# eprom-programmer.net
KiCad netlist of a schematic drawn in EAGLE
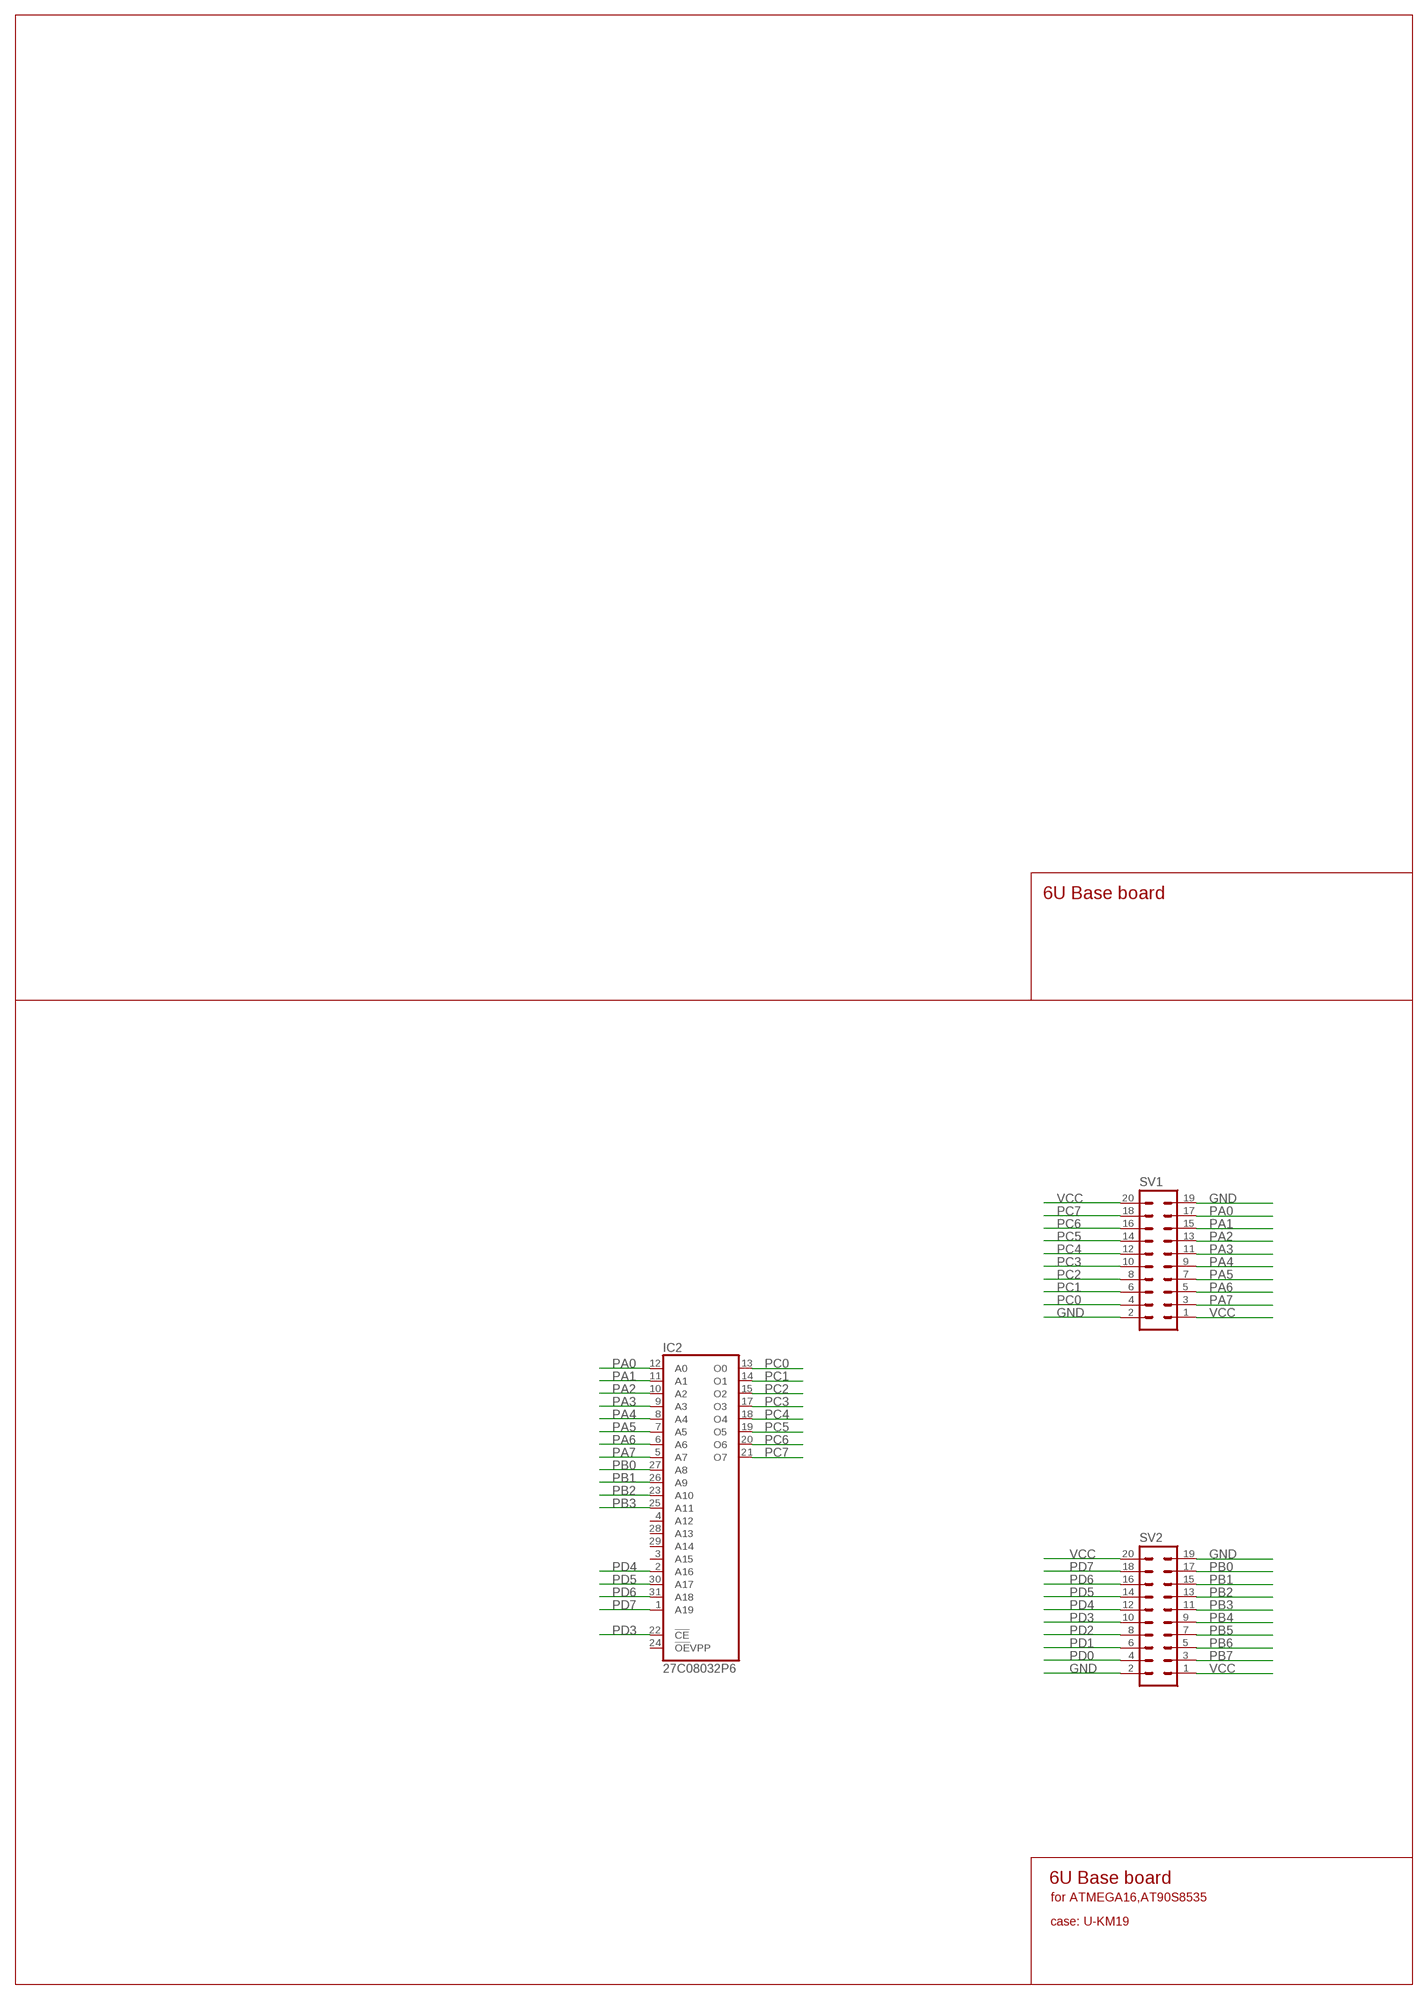
[diagram p0: schematic, sheet 1]

(export (version "E")
  (design (tool "Eeschema 10.0.6"))
  (components
    (comp (ref "IC2")
      (value "27C08032P6")
      (footprint "eagle-import:DIL32")
      (fields (field (name "MPN") "AT27C080-90PU"))
      (libsource (lib "eagle-import") (part "27C08032P6"))
    )
    (comp (ref "SV1")
      (value "MA10-2")
      (footprint "eagle-import:MA10-2")
      (libsource (lib "eagle-import") (part "MA10-2"))
    )
    (comp (ref "SV2")
      (value "MA10-2")
      (footprint "eagle-import:MA10-2")
      (libsource (lib "eagle-import") (part "MA10-2"))
    )
  )
  (nets
    (net (code "1") (name "/GND") (class "Default")
      (node (ref "SV1") (pin "19") (pinfunction "19_19") (pintype "passive"))
      (node (ref "SV1") (pin "2") (pinfunction "2_2") (pintype "passive"))
      (node (ref "SV2") (pin "19") (pinfunction "19_19") (pintype "passive"))
      (node (ref "SV2") (pin "2") (pinfunction "2_2") (pintype "passive"))
    )
    (net (code "2") (name "/PA0") (class "Default")
      (node (ref "IC2") (pin "12") (pinfunction "A0_12") (pintype "input"))
      (node (ref "SV1") (pin "17") (pinfunction "17_17") (pintype "passive"))
    )
    (net (code "3") (name "/PA1") (class "Default")
      (node (ref "IC2") (pin "11") (pinfunction "A1_11") (pintype "input"))
      (node (ref "SV1") (pin "15") (pinfunction "15_15") (pintype "passive"))
    )
    (net (code "4") (name "/PA2") (class "Default")
      (node (ref "IC2") (pin "10") (pinfunction "A2_10") (pintype "input"))
      (node (ref "SV1") (pin "13") (pinfunction "13_13") (pintype "passive"))
    )
    (net (code "5") (name "/PA3") (class "Default")
      (node (ref "IC2") (pin "9") (pinfunction "A3_9") (pintype "input"))
      (node (ref "SV1") (pin "11") (pinfunction "11_11") (pintype "passive"))
    )
    (net (code "6") (name "/PA4") (class "Default")
      (node (ref "IC2") (pin "8") (pinfunction "A4_8") (pintype "input"))
      (node (ref "SV1") (pin "9") (pinfunction "9_9") (pintype "passive"))
    )
    (net (code "7") (name "/PA5") (class "Default")
      (node (ref "IC2") (pin "7") (pinfunction "A5_7") (pintype "input"))
      (node (ref "SV1") (pin "7") (pinfunction "7_7") (pintype "passive"))
    )
    (net (code "8") (name "/PA6") (class "Default")
      (node (ref "IC2") (pin "6") (pinfunction "A6_6") (pintype "input"))
      (node (ref "SV1") (pin "5") (pinfunction "5_5") (pintype "passive"))
    )
    (net (code "9") (name "/PA7") (class "Default")
      (node (ref "IC2") (pin "5") (pinfunction "A7_5") (pintype "input"))
      (node (ref "SV1") (pin "3") (pinfunction "3_3") (pintype "passive"))
    )
    (net (code "10") (name "/PB0") (class "Default")
      (node (ref "IC2") (pin "27") (pinfunction "A8_27") (pintype "input"))
      (node (ref "SV2") (pin "17") (pinfunction "17_17") (pintype "passive"))
    )
    (net (code "11") (name "/PB1") (class "Default")
      (node (ref "IC2") (pin "26") (pinfunction "A9_26") (pintype "input"))
      (node (ref "SV2") (pin "15") (pinfunction "15_15") (pintype "passive"))
    )
    (net (code "12") (name "/PB2") (class "Default")
      (node (ref "IC2") (pin "23") (pinfunction "A10_23") (pintype "input"))
      (node (ref "SV2") (pin "13") (pinfunction "13_13") (pintype "passive"))
    )
    (net (code "13") (name "/PB3") (class "Default")
      (node (ref "IC2") (pin "25") (pinfunction "A11_25") (pintype "input"))
      (node (ref "SV2") (pin "11") (pinfunction "11_11") (pintype "passive"))
    )
    (net (code "14") (name "/PB4") (class "Default")
      (node (ref "SV2") (pin "9") (pinfunction "9_9") (pintype "passive"))
    )
    (net (code "15") (name "/PB5") (class "Default")
      (node (ref "SV2") (pin "7") (pinfunction "7_7") (pintype "passive"))
    )
    (net (code "16") (name "/PB6") (class "Default")
      (node (ref "SV2") (pin "5") (pinfunction "5_5") (pintype "passive"))
    )
    (net (code "17") (name "/PB7") (class "Default")
      (node (ref "SV2") (pin "3") (pinfunction "3_3") (pintype "passive"))
    )
    (net (code "18") (name "/PC0") (class "Default")
      (node (ref "IC2") (pin "13") (pinfunction "O0_13") (pintype "tri_state"))
      (node (ref "SV1") (pin "4") (pinfunction "4_4") (pintype "passive"))
    )
    (net (code "19") (name "/PC1") (class "Default")
      (node (ref "IC2") (pin "14") (pinfunction "O1_14") (pintype "tri_state"))
      (node (ref "SV1") (pin "6") (pinfunction "6_6") (pintype "passive"))
    )
    (net (code "20") (name "/PC2") (class "Default")
      (node (ref "IC2") (pin "15") (pinfunction "O2_15") (pintype "tri_state"))
      (node (ref "SV1") (pin "8") (pinfunction "8_8") (pintype "passive"))
    )
    (net (code "21") (name "/PC3") (class "Default")
      (node (ref "IC2") (pin "17") (pinfunction "O3_17") (pintype "tri_state"))
      (node (ref "SV1") (pin "10") (pinfunction "10_10") (pintype "passive"))
    )
    (net (code "22") (name "/PC4") (class "Default")
      (node (ref "IC2") (pin "18") (pinfunction "O4_18") (pintype "tri_state"))
      (node (ref "SV1") (pin "12") (pinfunction "12_12") (pintype "passive"))
    )
    (net (code "23") (name "/PC5") (class "Default")
      (node (ref "IC2") (pin "19") (pinfunction "O5_19") (pintype "tri_state"))
      (node (ref "SV1") (pin "14") (pinfunction "14_14") (pintype "passive"))
    )
    (net (code "24") (name "/PC6") (class "Default")
      (node (ref "IC2") (pin "20") (pinfunction "O6_20") (pintype "tri_state"))
      (node (ref "SV1") (pin "16") (pinfunction "16_16") (pintype "passive"))
    )
    (net (code "25") (name "/PC7") (class "Default")
      (node (ref "IC2") (pin "21") (pinfunction "O7_21") (pintype "tri_state"))
      (node (ref "SV1") (pin "18") (pinfunction "18_18") (pintype "passive"))
    )
    (net (code "26") (name "/PD0") (class "Default")
      (node (ref "SV2") (pin "4") (pinfunction "4_4") (pintype "passive"))
    )
    (net (code "27") (name "/PD1") (class "Default")
      (node (ref "SV2") (pin "6") (pinfunction "6_6") (pintype "passive"))
    )
    (net (code "28") (name "/PD2") (class "Default")
      (node (ref "SV2") (pin "8") (pinfunction "8_8") (pintype "passive"))
    )
    (net (code "29") (name "/PD3") (class "Default")
      (node (ref "IC2") (pin "22") (pinfunction "~{CE}_22") (pintype "input"))
      (node (ref "SV2") (pin "10") (pinfunction "10_10") (pintype "passive"))
    )
    (net (code "30") (name "/PD4") (class "Default")
      (node (ref "IC2") (pin "2") (pinfunction "A16_2") (pintype "input"))
      (node (ref "SV2") (pin "12") (pinfunction "12_12") (pintype "passive"))
    )
    (net (code "31") (name "/PD5") (class "Default")
      (node (ref "IC2") (pin "30") (pinfunction "A17_30") (pintype "input"))
      (node (ref "SV2") (pin "14") (pinfunction "14_14") (pintype "passive"))
    )
    (net (code "32") (name "/PD6") (class "Default")
      (node (ref "IC2") (pin "31") (pinfunction "A18_31") (pintype "input"))
      (node (ref "SV2") (pin "16") (pinfunction "16_16") (pintype "passive"))
    )
    (net (code "33") (name "/PD7") (class "Default")
      (node (ref "IC2") (pin "1") (pinfunction "A19_1") (pintype "input"))
      (node (ref "SV2") (pin "18") (pinfunction "18_18") (pintype "passive"))
    )
    (net (code "34") (name "/VCC") (class "Default")
      (node (ref "SV1") (pin "1") (pinfunction "1_1") (pintype "passive"))
      (node (ref "SV1") (pin "20") (pinfunction "20_20") (pintype "passive"))
      (node (ref "SV2") (pin "1") (pinfunction "1_1") (pintype "passive"))
      (node (ref "SV2") (pin "20") (pinfunction "20_20") (pintype "passive"))
    )
    (net (code "35") (name "unconnected-(IC2A-A12-Pad4)") (class "Default")
      (node (ref "IC2") (pin "4") (pinfunction "A12_4") (pintype "input"))
    )
    (net (code "36") (name "unconnected-(IC2A-A13-Pad28)") (class "Default")
      (node (ref "IC2") (pin "28") (pinfunction "A13_28") (pintype "input"))
    )
    (net (code "37") (name "unconnected-(IC2A-A14-Pad29)") (class "Default")
      (node (ref "IC2") (pin "29") (pinfunction "A14_29") (pintype "input"))
    )
    (net (code "38") (name "unconnected-(IC2A-A15-Pad3)") (class "Default")
      (node (ref "IC2") (pin "3") (pinfunction "A15_3") (pintype "input"))
    )
    (net (code "39") (name "unconnected-(IC2A-~{OE}VPP-Pad24)") (class "Default")
      (node (ref "IC2") (pin "24") (pinfunction "~{OE}VPP_24") (pintype "input"))
    )
  )
)
